# PWM_Output.net
KiCad netlist of a schematic drawn in Altium Designer
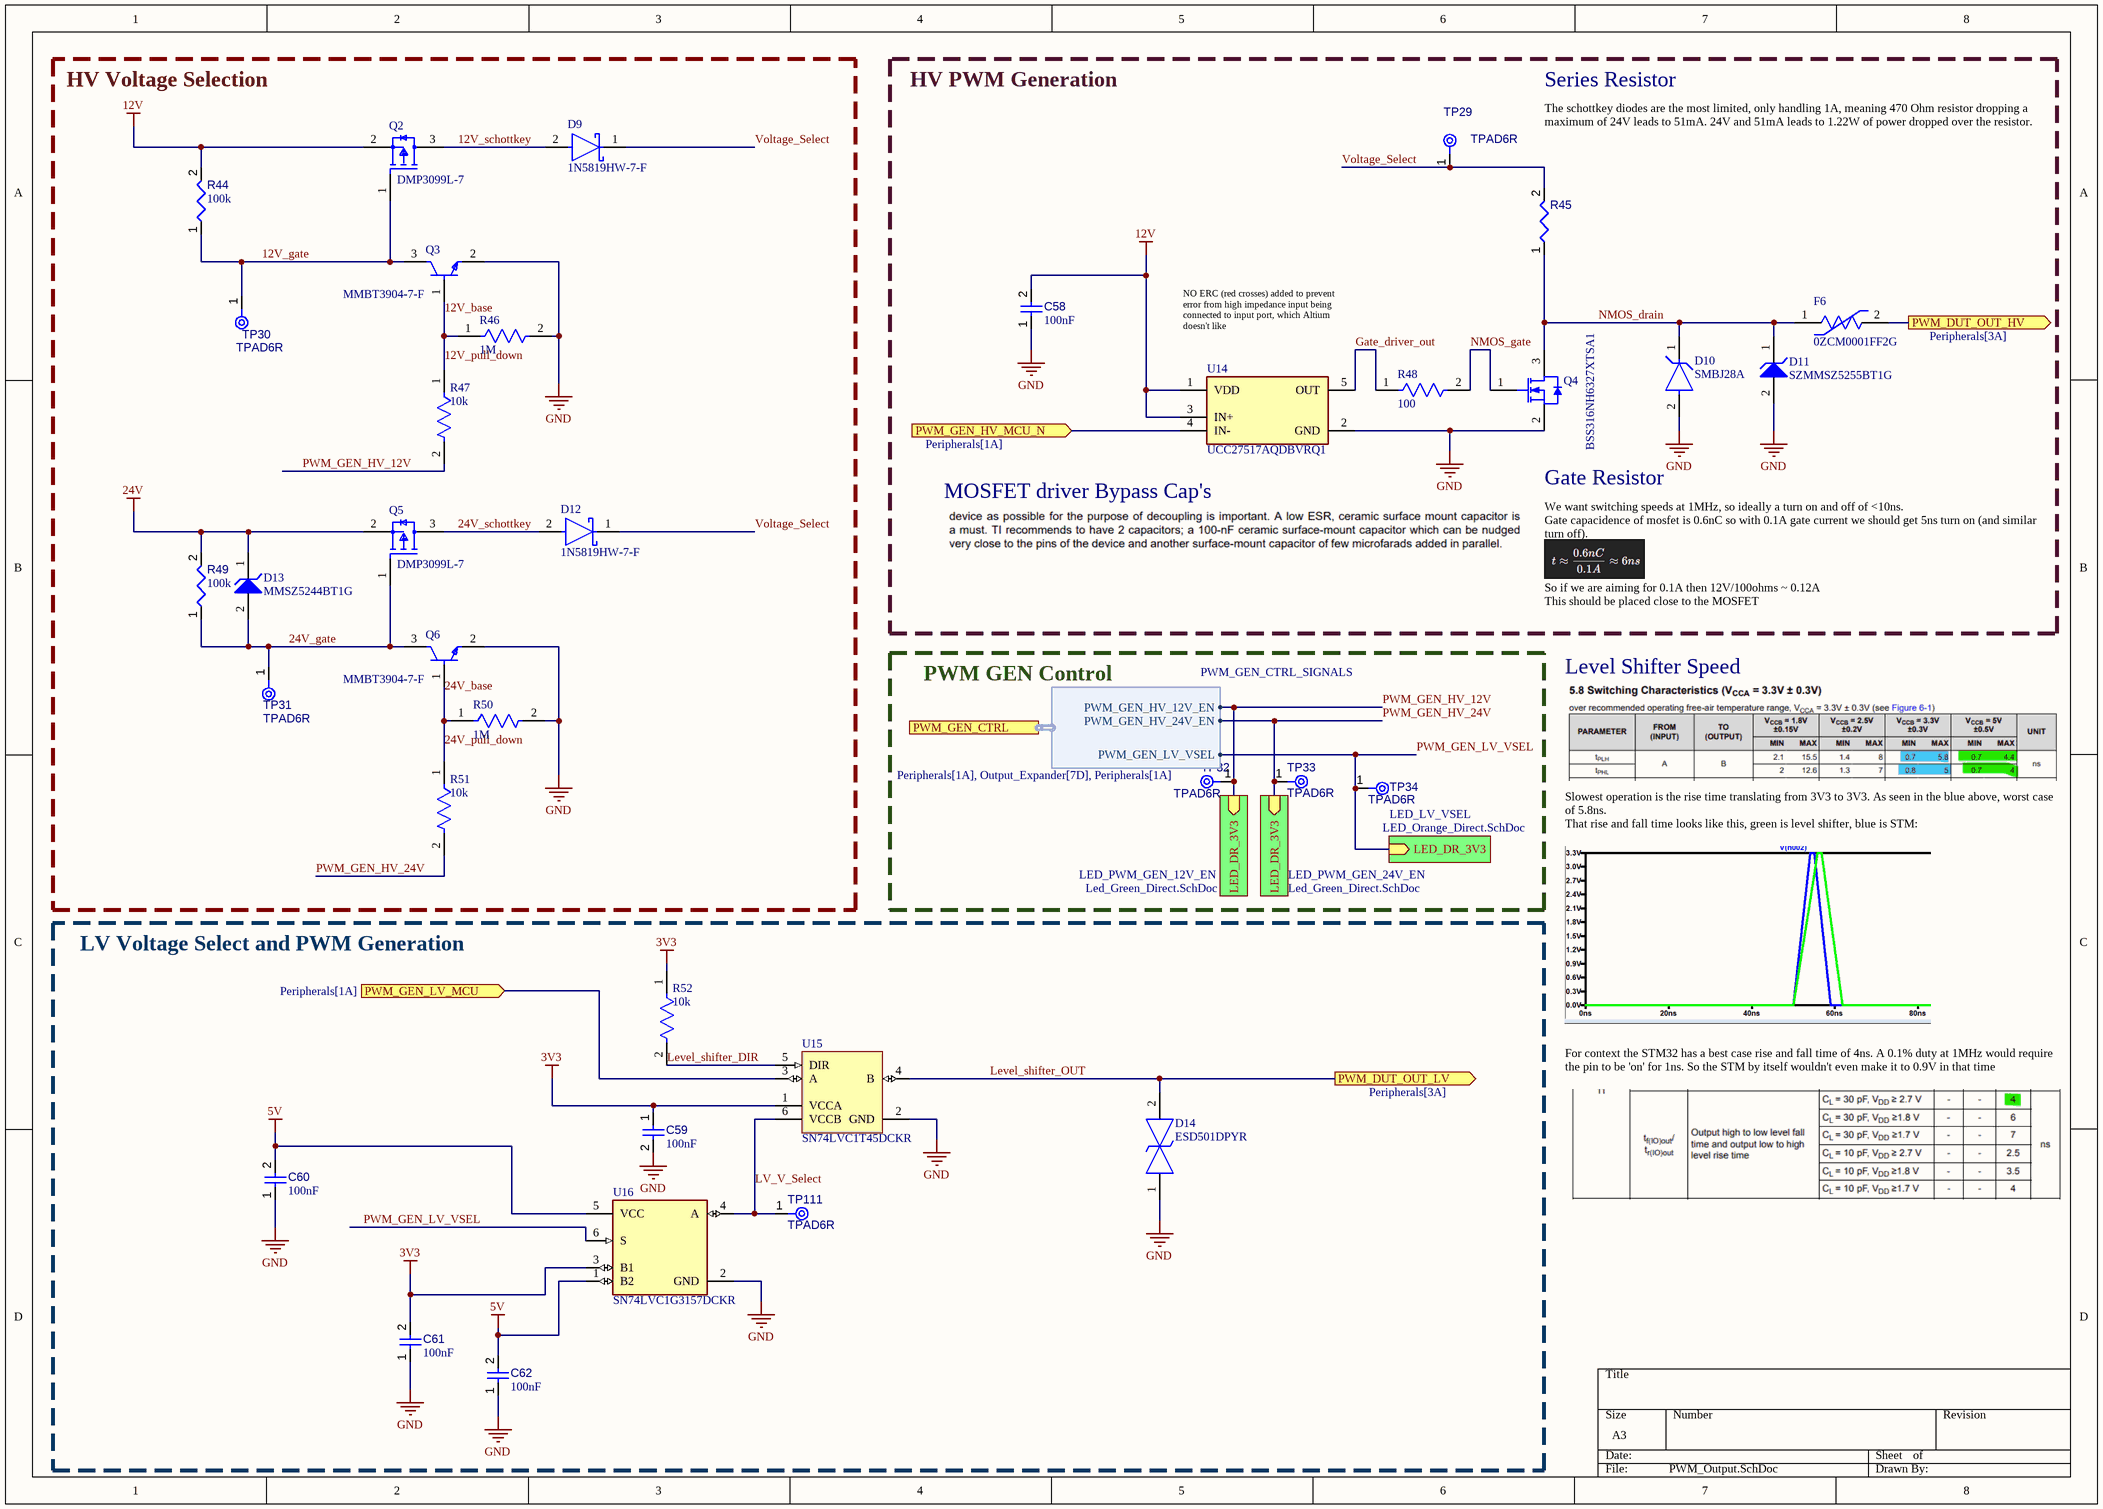
[diagram p0:  PWM_Output.SchDoc]

(export (version "E")
  (design (tool "Eeschema 10.0.6"))
  (components
    (comp (ref "C58")
      (value "100nF")
      (footprint "CAPC1608X90X40NL10T20")
      (description "Chip Capacitor, 100 nF, +/- 10%, 50 V, 0603 (1608 Metric)")
      (fields (field (name "TOLERANCE") "10%") (field (name "Comment") "Capacitor 100 nF +/-10% 50 V 0603"))
      (libsource (lib "HIL RIG FYP") (part "CAP-NP-2"))
    )
    (comp (ref "C59")
      (value "100nF")
      (footprint "CAPC1608X90X40NL10T20")
      (description "Chip Capacitor, 100 nF, +/- 10%, 50 V, 0603 (1608 Metric)")
      (fields (field (name "TOLERANCE") "10%") (field (name "Comment") "Capacitor 100 nF +/-10% 50 V 0603"))
      (libsource (lib "HIL RIG FYP") (part "CAP-NP-2"))
    )
    (comp (ref "C60")
      (value "100nF")
      (footprint "CAPC1608X90X40NL10T20")
      (description "Chip Capacitor, 100 nF, +/- 10%, 50 V, 0603 (1608 Metric)")
      (fields (field (name "TOLERANCE") "10%") (field (name "Comment") "Capacitor 100 nF +/-10% 50 V 0603"))
      (libsource (lib "HIL RIG FYP") (part "CAP-NP-2"))
    )
    (comp (ref "C61")
      (value "100nF")
      (footprint "CAPC1608X90X40NL10T20")
      (description "Chip Capacitor, 100 nF, +/- 10%, 50 V, 0603 (1608 Metric)")
      (fields (field (name "TOLERANCE") "10%") (field (name "Comment") "Capacitor 100 nF +/-10% 50 V 0603"))
      (libsource (lib "HIL RIG FYP") (part "CAP-NP-2"))
    )
    (comp (ref "C62")
      (value "100nF")
      (footprint "CAPC1608X90X40NL10T20")
      (description "Chip Capacitor, 100 nF, +/- 10%, 50 V, 0603 (1608 Metric)")
      (fields (field (name "TOLERANCE") "10%") (field (name "Comment") "Capacitor 100 nF +/-10% 50 V 0603"))
      (libsource (lib "HIL RIG FYP") (part "CAP-NP-2"))
    )
    (comp (ref "D9")
      (value "1N5819HW-7-F")
      (footprint "FP-SOD123-IPC_C")
      (description "1N5819HW Series 40 V 1 A Surface Mount Schottky Barrier Rectifier - SOD-123")
      (libsource (lib "HIL RIG FYP") (part "1d6ec82d83fb6aee721767c19dac4b9"))
    )
    (comp (ref "D10")
      (value "SMBJ28A")
      (footprint "FP-SMBJ-MFG")
      (description "Tvs Diodes & Esd Suppressors; SMBJ28A; Littelfuse; 28 V; 45.4 V; 31.1 V; 31.1 V")
      (fields (field (name "VOLTAGE") "28V"))
      (libsource (lib "HIL RIG FYP") (part "f813f71cba58e380607f5dd3caf9714"))
    )
    (comp (ref "D11")
      (value "SZMMSZ5255BT1G")
      (footprint "ONSC-SOD-123-2-425-04_V")
      (description "DIODE ZENER 28V 500MW SOD123 / Zener Diode 28 V 500 mW ±5% Surface Mount SOD-123")
      (fields (field (name "TOLERANCE") "5%"))
      (libsource (lib "HIL RIG FYP") (part "ONSC-K1A2-2"))
    )
    (comp (ref "D12")
      (value "1N5819HW-7-F")
      (footprint "FP-SOD123-IPC_C")
      (description "1N5819HW Series 40 V 1 A Surface Mount Schottky Barrier Rectifier - SOD-123")
      (libsource (lib "HIL RIG FYP") (part "1d6ec82d83fb6aee721767c19dac4b9"))
    )
    (comp (ref "D13")
      (value "MMSZ5244BT1G")
      (footprint "ONSC-SOD-123-2-425-04_V")
      (description "MMSZ5244BT1 Series 500 mW 10 mA 14 V SMT Zener Voltage Regulator - SOD-123")
      (fields (field (name "TOLERANCE") "5%"))
      (libsource (lib "HIL RIG FYP") (part "ONSC-K1A2-2"))
    )
    (comp (ref "D14")
      (value "ESD501DPYR")
      (footprint "ESD501DPYR")
      (description "ESD Protection Diodes / TVS Diodes 12V bidirectional ul tra-low capacitance")
      (fields (field (name "MOUSER PART NUMBER") "595-ESD501DPYR"))
      (libsource (lib "HIL RIG FYP") (part "ESD501DPYR"))
    )
    (comp (ref "F6")
      (value "0ZCM0001FF2G")
      (footprint "FP-0ZCM0001FF2G-MFG")
      (description "Prices include import duty and tax. RESETTABLE PTC FUSE, SMD, 0603 SIZE, 10MA, 60V;")
      (libsource (lib "HIL RIG FYP") (part "1c6d77a0208143737455a0c7eb396be"))
    )
    (comp (ref "Q2")
      (value "DMP3099L-7")
      (footprint "FP-SOT23-IPC_A")
      (description "DMP3099L Series 30 V 65 mOhm P-Channel Enhancement Mode Mosfet - SOT-23-3")
      (libsource (lib "HIL RIG FYP") (part "d876440acba04c58a9f817a20952145"))
    )
    (comp (ref "Q3")
      (value "MMBT3904-7-F")
      (footprint "FP-SOT23-IPC_A")
      (description "Transistor General Purpose BJT NPN 40 Volt 0.2A Automotive 3-Pin SOT-23")
      (libsource (lib "HIL RIG FYP") (part "b44e953556f554d0102664c7d152cb4"))
    )
    (comp (ref "Q4")
      (value "BSS316NH6327XTSA1")
      (footprint "INF-PG-SOT23_L")
      (description "Power MOSFET, N Channel, 30 V, 1.4 A, 160 mOhm, SOT-23, 3 Pins, Surface Mount")
      (libsource (lib "HIL RIG FYP") (part "INF-NEMOS-GSD-3"))
    )
    (comp (ref "Q5")
      (value "DMP3099L-7")
      (footprint "FP-SOT23-IPC_A")
      (description "DMP3099L Series 30 V 65 mOhm P-Channel Enhancement Mode Mosfet - SOT-23-3")
      (libsource (lib "HIL RIG FYP") (part "d876440acba04c58a9f817a20952145"))
    )
    (comp (ref "Q6")
      (value "MMBT3904-7-F")
      (footprint "FP-SOT23-IPC_A")
      (description "Transistor General Purpose BJT NPN 40 Volt 0.2A Automotive 3-Pin SOT-23")
      (libsource (lib "HIL RIG FYP") (part "b44e953556f554d0102664c7d152cb4"))
    )
    (comp (ref "R44")
      (value "100k")
      (footprint "FP-AC0603-IPC_C")
      (description "Res Thick Film 0603 100K Ohm 1% 0.1W(1/10W) ±100ppm/C Pad SMD T/R Automotive")
      (fields (field (name "TOLERANCE") "1%") (field (name "Comment") "AC0603FR-07100KL"))
      (libsource (lib "HIL RIG FYP") (part "RES-2"))
    )
    (comp (ref "R45")
      (value "HOCR2512-2W-470R-5%")
      (footprint "RESC6432X95N")
      (description "2W Ceramic resistor ±5% 470Ω 2512 Chip Resistor - Surface Mount ROHS")
      (libsource (lib "HIL RIG FYP") (part "RES-2"))
    )
    (comp (ref "R46")
      (value "1M")
      (footprint "FP-CRGP0603-IPC_C")
      (description "Res Thick Film 0603 1M Ohm 1% 0.25W(1/4W) ±100ppm/C Pad SMD T/R Automotive AEC-Q200")
      (fields (field (name "TOLERANCE") "1%") (field (name "Comment") "CRGP0603F1M0"))
      (libsource (lib "HIL RIG FYP") (part "1029c3af85768c4190bb7ad29bc67b5"))
    )
    (comp (ref "R47")
      (value "10k")
      (footprint "FP-RT0603-IPC_C")
      (description "Res Thin Film 0603 10K Ohm 0.1% 1/10W ¦25ppm/¦C SMD Paper T/R")
      (fields (field (name "TOLERANCE") "0.1%") (field (name "Comment") "RT0603BRD0710KL"))
      (libsource (lib "HIL RIG FYP") (part "1029c3af85768c4190bb7ad29bc67b5"))
    )
    (comp (ref "R48")
      (value "100")
      (footprint "FP-CRGP2512-IPC_A")
      (description "2W Thick Film Resistors ±1% ±200ppm/℃ 100Ω 2512 Chip Resistor - Surface Mount ROHS")
      (fields (field (name "TOLERANCE") "1%") (field (name "Comment") "CRGP2512F100R"))
      (libsource (lib "HIL RIG FYP") (part "1029c3af85768c4190bb7ad29bc67b5"))
    )
    (comp (ref "R49")
      (value "100k")
      (footprint "FP-AC0603-IPC_C")
      (description "Res Thick Film 0603 100K Ohm 1% 0.1W(1/10W) ±100ppm/C Pad SMD T/R Automotive")
      (fields (field (name "TOLERANCE") "1%") (field (name "Comment") "AC0603FR-07100KL"))
      (libsource (lib "HIL RIG FYP") (part "RES-2"))
    )
    (comp (ref "R50")
      (value "1M")
      (footprint "FP-CRGP0603-IPC_C")
      (description "Res Thick Film 0603 1M Ohm 1% 0.25W(1/4W) ±100ppm/C Pad SMD T/R Automotive AEC-Q200")
      (fields (field (name "TOLERANCE") "1%") (field (name "Comment") "CRGP0603F1M0"))
      (libsource (lib "HIL RIG FYP") (part "1029c3af85768c4190bb7ad29bc67b5"))
    )
    (comp (ref "R51")
      (value "10k")
      (footprint "FP-RT0603-IPC_C")
      (description "Res Thin Film 0603 10K Ohm 0.1% 1/10W ¦25ppm/¦C SMD Paper T/R")
      (fields (field (name "TOLERANCE") "0.1%") (field (name "Comment") "RT0603BRD0710KL"))
      (libsource (lib "HIL RIG FYP") (part "1029c3af85768c4190bb7ad29bc67b5"))
    )
    (comp (ref "R52")
      (value "10k")
      (footprint "FP-RT0603-IPC_C")
      (description "Res Thin Film 0603 10K Ohm 0.1% 1/10W ¦25ppm/¦C SMD Paper T/R")
      (fields (field (name "TOLERANCE") "0.1%") (field (name "Comment") "RT0603BRD0710KL"))
      (libsource (lib "HIL RIG FYP") (part "1029c3af85768c4190bb7ad29bc67b5"))
    )
    (comp (ref "TP29")
      (value "TPAD6R")
      (footprint "TP06R")
      (description "0.6mm round")
      (libsource (lib "HIL RIG FYP") (part "CMP-001-0001-4"))
    )
    (comp (ref "TP30")
      (value "TPAD6R")
      (footprint "TP06R")
      (description "0.6mm round")
      (libsource (lib "HIL RIG FYP") (part "CMP-001-0001-4"))
    )
    (comp (ref "TP31")
      (value "TPAD6R")
      (footprint "TP06R")
      (description "0.6mm round")
      (libsource (lib "HIL RIG FYP") (part "CMP-001-0001-4"))
    )
    (comp (ref "TP32")
      (value "TPAD6R")
      (footprint "TP06R")
      (description "0.6mm round")
      (libsource (lib "HIL RIG FYP") (part "CMP-001-0001-4"))
    )
    (comp (ref "TP33")
      (value "TPAD6R")
      (footprint "TP06R")
      (description "0.6mm round")
      (libsource (lib "HIL RIG FYP") (part "CMP-001-0001-4"))
    )
    (comp (ref "TP34")
      (value "TPAD6R")
      (footprint "TP06R")
      (description "0.6mm round")
      (libsource (lib "HIL RIG FYP") (part "CMP-001-0001-4"))
    )
    (comp (ref "TP111")
      (value "TPAD6R")
      (footprint "TP06R")
      (description "0.6mm round")
      (libsource (lib "HIL RIG FYP") (part "CMP-001-0001-4"))
    )
    (comp (ref "U14")
      (value "UCC27517AQDBVRQ1")
      (footprint "FP-DBV0005A-IPC_B")
      (libsource (lib "HIL RIG FYP") (part "852976a250a43ce973e2ce06d98181f"))
    )
    (comp (ref "U15")
      (value "SN74LVC1T45DCKR")
      (footprint "DCK0006A_M")
      (description "Translators, Level Shifters bidirectional 420Mbps 1.65V~5.5VCCA 1.65V~5.5VCCB")
      (libsource (lib "HIL RIG FYP") (part "TI-SN74XVC1T45-6"))
    )
    (comp (ref "U16")
      (value "SN74LVC1G3157DCKR")
      (footprint "FP-DCK0006A-MFG")
      (description "Single-pole Double-throw Analog Switch SPDT, 1 Func, 1 Channel, Cmos, PDSO6")
      (libsource (lib "HIL RIG FYP") (part "0261a57985ab8eeec66806cf7caee19"))
    )
  )
  (nets
    (net (code "2") (name "/12V_base") (class "Default")
      (node (ref "Q3") (pin "1") (pinfunction "B_1") (pintype "passive"))
      (node (ref "R46") (pin "1") (pinfunction "1_1") (pintype "passive"))
      (node (ref "R47") (pin "1") (pinfunction "1_1") (pintype "passive"))
    )
    (net (code "3") (name "/12V_gate") (class "Default")
      (node (ref "Q2") (pin "1") (pinfunction "G_1") (pintype "passive"))
      (node (ref "Q3") (pin "3") (pinfunction "C_3") (pintype "passive"))
      (node (ref "R44") (pin "1") (pinfunction "1_1") (pintype "passive"))
      (node (ref "TP30") (pin "1") (pinfunction "TP_1") (pintype "passive"))
    )
    (net (code "4") (name "/12V_schottkey") (class "Default")
      (node (ref "D9") (pin "2") (pinfunction "A_2") (pintype "passive"))
      (node (ref "Q2") (pin "3") (pinfunction "D_3") (pintype "passive"))
    )
    (net (code "5") (name "/24V_base") (class "Default")
      (node (ref "Q6") (pin "1") (pinfunction "B_1") (pintype "passive"))
      (node (ref "R50") (pin "1") (pinfunction "1_1") (pintype "passive"))
      (node (ref "R51") (pin "1") (pinfunction "1_1") (pintype "passive"))
    )
    (net (code "6") (name "/24V_gate") (class "Default")
      (node (ref "D13") (pin "2") (pinfunction "A_2") (pintype "passive"))
      (node (ref "Q5") (pin "1") (pinfunction "G_1") (pintype "passive"))
      (node (ref "Q6") (pin "3") (pinfunction "C_3") (pintype "passive"))
      (node (ref "R49") (pin "1") (pinfunction "1_1") (pintype "passive"))
      (node (ref "TP31") (pin "1") (pinfunction "TP_1") (pintype "passive"))
    )
    (net (code "7") (name "/24V_schottkey") (class "Default")
      (node (ref "D12") (pin "2") (pinfunction "A_2") (pintype "passive"))
      (node (ref "Q5") (pin "3") (pinfunction "D_3") (pintype "passive"))
    )
    (net (code "8") (name "/Gate_driver_out") (class "Default")
      (node (ref "R48") (pin "1") (pinfunction "1_1") (pintype "passive"))
      (node (ref "U14") (pin "5") (pinfunction "OUT_5") (pintype "passive"))
    )
    (net (code "9") (name "/LV_V_Select") (class "Default")
      (node (ref "TP111") (pin "1") (pinfunction "TP_1") (pintype "passive"))
      (node (ref "U15") (pin "6") (pinfunction "VCCB_6") (pintype "power_in"))
      (node (ref "U16") (pin "4") (pinfunction "A_4") (pintype "bidirectional"))
    )
    (net (code "10") (name "/Level_shifter_DIR") (class "Default")
      (node (ref "R52") (pin "2") (pinfunction "2_2") (pintype "passive"))
      (node (ref "U15") (pin "5") (pinfunction "DIR_5") (pintype "input"))
    )
    (net (code "11") (name "/Level_shifter_OUT") (class "Default")
      (node (ref "D14") (pin "2") (pinfunction "2_2") (pintype "passive"))
      (node (ref "U15") (pin "4") (pinfunction "B_4") (pintype "bidirectional"))
    )
    (net (code "12") (name "/NMOS_drain") (class "Default")
      (node (ref "D10") (pin "1") (pinfunction "C_1") (pintype "passive"))
      (node (ref "D11") (pin "1") (pinfunction "K_1") (pintype "passive"))
      (node (ref "F6") (pin "1") (pinfunction "1_1") (pintype "passive"))
      (node (ref "Q4") (pin "3") (pinfunction "DRAIN_3") (pintype "passive"))
      (node (ref "R45") (pin "1") (pinfunction "1_1") (pintype "passive"))
    )
    (net (code "13") (name "/NMOS_gate") (class "Default")
      (node (ref "Q4") (pin "1") (pinfunction "GATE_1") (pintype "passive"))
      (node (ref "R48") (pin "2") (pinfunction "2_2") (pintype "passive"))
    )
    (net (code "14") (name "/PWM_DUT_OUT_HV") (class "Default")
      (node (ref "F6") (pin "2") (pinfunction "2_2") (pintype "passive"))
    )
    (net (code "15") (name "/PWM_GEN_HV_12V") (class "Default")
      (node (ref "R47") (pin "2") (pinfunction "2_2") (pintype "passive"))
      (node (ref "TP32") (pin "1") (pinfunction "TP_1") (pintype "passive"))
    )
    (net (code "16") (name "/PWM_GEN_HV_24V") (class "Default")
      (node (ref "R51") (pin "2") (pinfunction "2_2") (pintype "passive"))
      (node (ref "TP33") (pin "1") (pinfunction "TP_1") (pintype "passive"))
    )
    (net (code "17") (name "/PWM_GEN_HV_MCU_N") (class "Default")
      (node (ref "U14") (pin "4") (pinfunction "IN-_4") (pintype "tri_state"))
    )
    (net (code "18") (name "/PWM_GEN_LV_MCU") (class "Default")
      (node (ref "U15") (pin "3") (pinfunction "A_3") (pintype "bidirectional"))
    )
    (net (code "19") (name "/PWM_GEN_LV_VSEL") (class "Default")
      (node (ref "TP34") (pin "1") (pinfunction "TP_1") (pintype "passive"))
      (node (ref "U16") (pin "6") (pinfunction "S_6") (pintype "input"))
    )
    (net (code "20") (name "/Voltage_Select") (class "Default")
      (node (ref "D12") (pin "1") (pinfunction "C_1") (pintype "passive"))
      (node (ref "D9") (pin "1") (pinfunction "C_1") (pintype "passive"))
      (node (ref "R45") (pin "2") (pinfunction "2_2") (pintype "passive"))
      (node (ref "TP29") (pin "1") (pinfunction "TP_1") (pintype "passive"))
    )
    (net (code "22") (name "3V3") (class "Default")
      (node (ref "C59") (pin "1") (pinfunction "1_1") (pintype "passive"))
      (node (ref "C61") (pin "2") (pinfunction "2_2") (pintype "passive"))
      (node (ref "R52") (pin "1") (pinfunction "1_1") (pintype "passive"))
      (node (ref "U15") (pin "1") (pinfunction "VCCA_1") (pintype "power_in"))
      (node (ref "U16") (pin "3") (pinfunction "B1_3") (pintype "bidirectional"))
    )
    (net (code "23") (name "5V") (class "Default")
      (node (ref "C60") (pin "2") (pinfunction "2_2") (pintype "passive"))
      (node (ref "C62") (pin "2") (pinfunction "2_2") (pintype "passive"))
      (node (ref "U16") (pin "1") (pinfunction "B2_1") (pintype "bidirectional"))
      (node (ref "U16") (pin "5") (pinfunction "VCC_5") (pintype "power_in"))
    )
    (net (code "24") (name "12V") (class "Default")
      (node (ref "C58") (pin "2") (pinfunction "2_2") (pintype "passive"))
      (node (ref "Q2") (pin "2") (pinfunction "S_2") (pintype "passive"))
      (node (ref "R44") (pin "2") (pinfunction "2_2") (pintype "passive"))
      (node (ref "U14") (pin "1") (pinfunction "VDD_1") (pintype "power_in"))
      (node (ref "U14") (pin "3") (pinfunction "IN+_3") (pintype "tri_state"))
    )
    (net (code "25") (name "24V") (class "Default")
      (node (ref "D13") (pin "1") (pinfunction "K_1") (pintype "passive"))
      (node (ref "Q5") (pin "2") (pinfunction "S_2") (pintype "passive"))
      (node (ref "R49") (pin "2") (pinfunction "2_2") (pintype "passive"))
    )
    (net (code "26") (name "GND") (class "Default")
      (node (ref "C58") (pin "1") (pinfunction "1_1") (pintype "passive"))
      (node (ref "C59") (pin "2") (pinfunction "2_2") (pintype "passive"))
      (node (ref "C60") (pin "1") (pinfunction "1_1") (pintype "passive"))
      (node (ref "C61") (pin "1") (pinfunction "1_1") (pintype "passive"))
      (node (ref "C62") (pin "1") (pinfunction "1_1") (pintype "passive"))
      (node (ref "D10") (pin "2") (pinfunction "A_2") (pintype "passive"))
      (node (ref "D11") (pin "2") (pinfunction "A_2") (pintype "passive"))
      (node (ref "D14") (pin "1") (pinfunction "1_1") (pintype "passive"))
      (node (ref "Q3") (pin "2") (pinfunction "E_2") (pintype "passive"))
      (node (ref "Q4") (pin "2") (pinfunction "SOURCE_2") (pintype "passive"))
      (node (ref "Q6") (pin "2") (pinfunction "E_2") (pintype "passive"))
      (node (ref "R46") (pin "2") (pinfunction "2_2") (pintype "passive"))
      (node (ref "R50") (pin "2") (pinfunction "2_2") (pintype "passive"))
      (node (ref "U14") (pin "2") (pinfunction "GND_2") (pintype "power_in"))
      (node (ref "U15") (pin "2") (pinfunction "GND_2") (pintype "power_in"))
      (node (ref "U16") (pin "2") (pinfunction "GND_2") (pintype "power_in"))
    )
  )
)
